# ATTAMI-Shield-serial.net
KiCad netlist of a schematic drawn in EAGLE
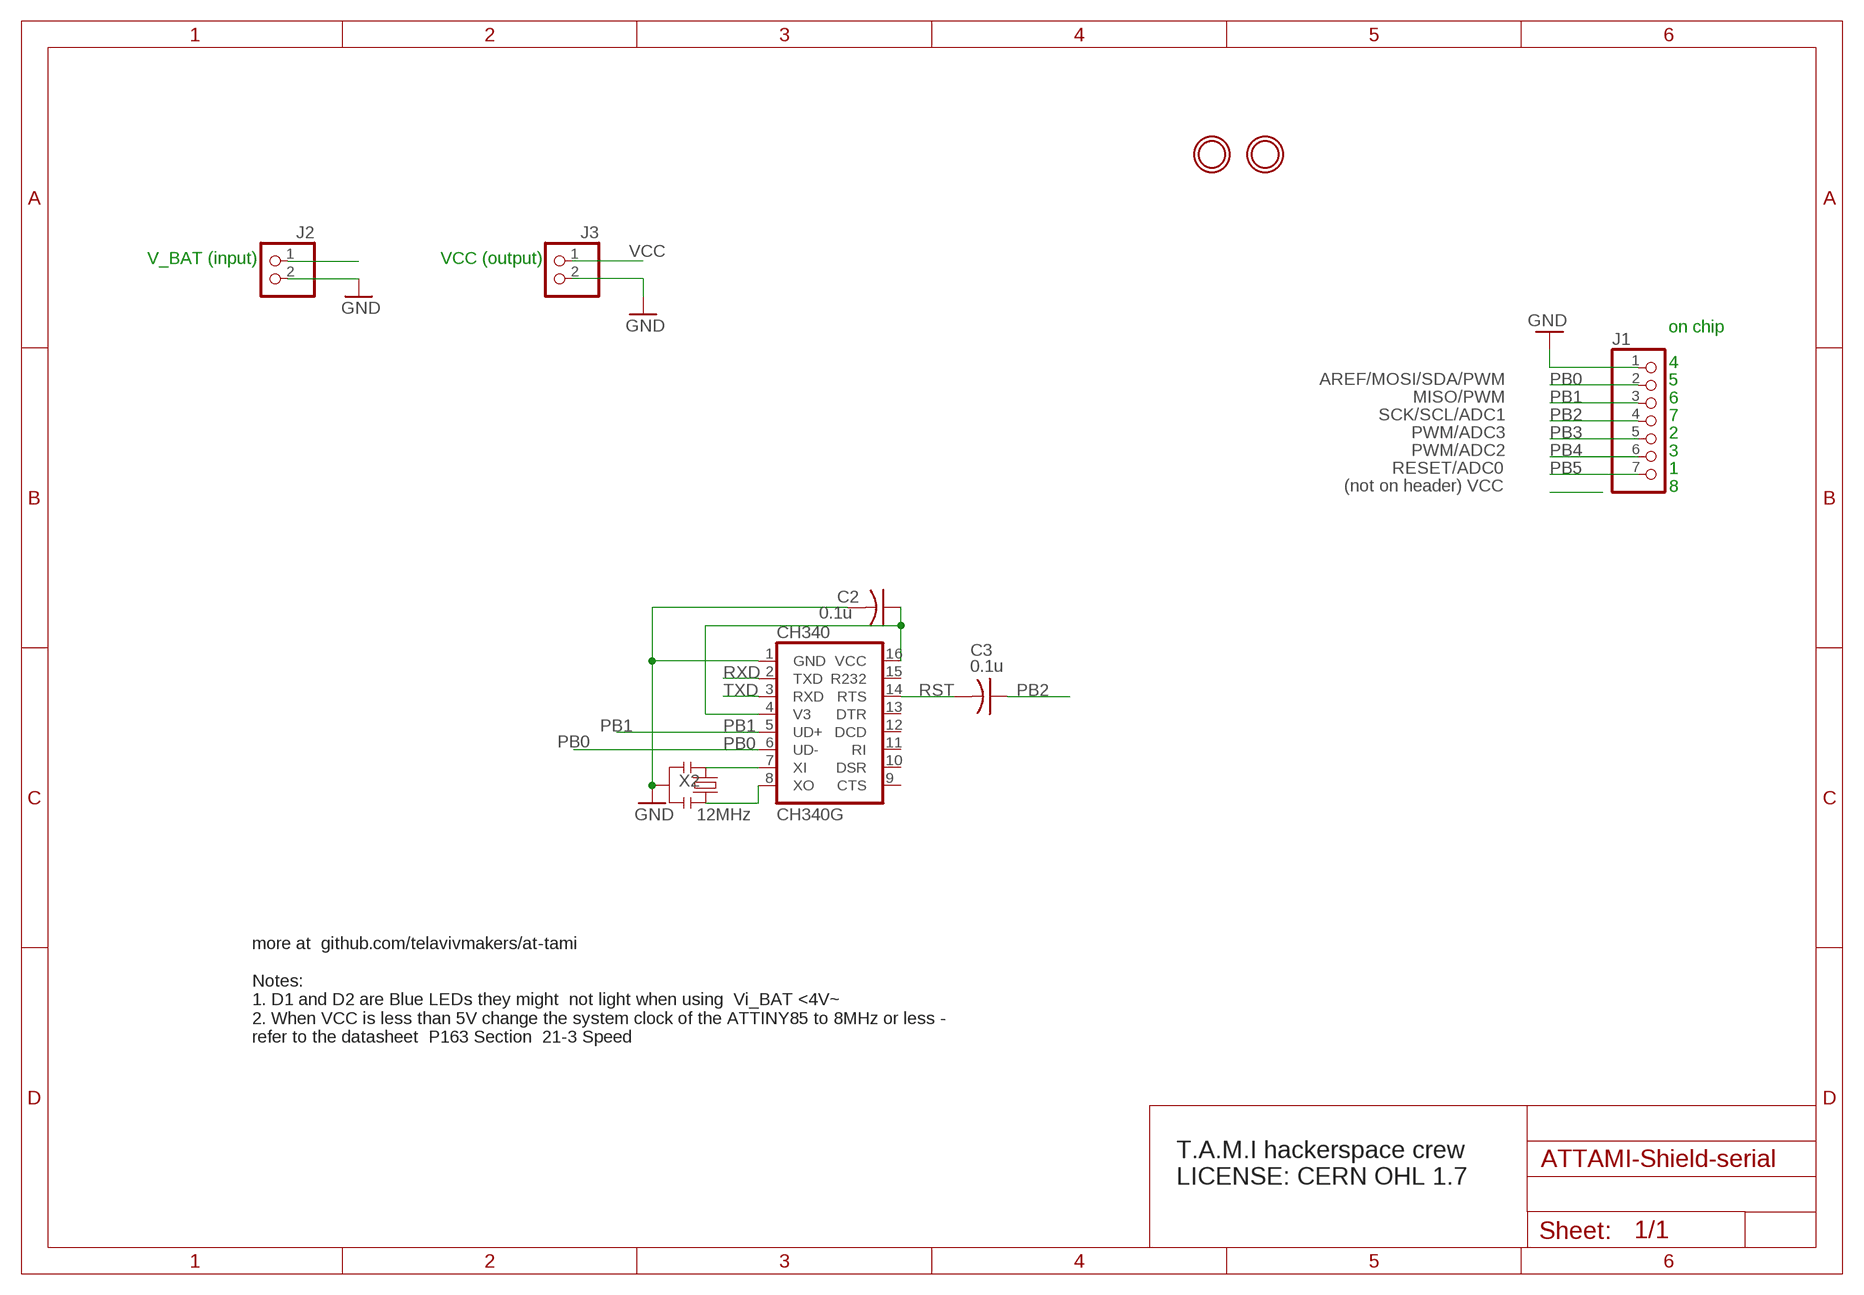
[diagram p0: schematic, sheet 1]

(export (version "E")
  (design (tool "Eeschema 10.0.6"))
  (components
    (comp (ref "C2")
      (value "0.1u")
      (footprint "eagle-import:C0603")
      (libsource (lib "eagle-import") (part "C-USC0603"))
    )
    (comp (ref "C3")
      (value "0.1u")
      (footprint "eagle-import:C0603")
      (libsource (lib "eagle-import") (part "C-USC0603"))
    )
    (comp (ref "CH340")
      (value "CH340G")
      (footprint "eagle-import:SO16")
      (libsource (lib "eagle-import") (part "CH340G"))
    )
    (comp (ref "J1")
      (value "HEADER-1X7ROUND")
      (footprint "eagle-import:1X07_ROUND")
      (libsource (lib "eagle-import") (part "HEADER-1X7ROUND"))
    )
    (comp (ref "J2")
      (value "HEADER-1X2ROUND")
      (footprint "eagle-import:1X02_ROUND")
      (libsource (lib "eagle-import") (part "HEADER-1X2ROUND"))
    )
    (comp (ref "J3")
      (value "HEADER-1X2ROUND")
      (footprint "eagle-import:1X02_ROUND")
      (libsource (lib "eagle-import") (part "HEADER-1X2ROUND"))
    )
    (comp (ref "U$1")
      (value "MOUNTINGHOLE2.0")
      (footprint "eagle-import:MOUNTINGHOLE_2.0_PLATED")
      (libsource (lib "eagle-import") (part "MOUNTINGHOLE2.0"))
    )
    (comp (ref "U$2")
      (value "MOUNTINGHOLE2.0")
      (footprint "eagle-import:MOUNTINGHOLE_2.0_PLATED")
      (libsource (lib "eagle-import") (part "MOUNTINGHOLE2.0"))
    )
    (comp (ref "X2")
      (value "12MHz")
      (footprint "eagle-import:RESONATOR-SMD")
      (libsource (lib "eagle-import") (part "RESONATORSMD"))
    )
  )
  (nets
    (net (code "1") (name "/PB0") (class "Default")
      (node (ref "CH340") (pin "6") (pinfunction "UD-_6") (pintype "bidirectional"))
      (node (ref "J1") (pin "2") (pinfunction "2_2") (pintype "passive"))
    )
    (net (code "2") (name "/PB1") (class "Default")
      (node (ref "CH340") (pin "5") (pinfunction "UD+_5") (pintype "bidirectional"))
      (node (ref "J1") (pin "3") (pinfunction "3_3") (pintype "passive"))
    )
    (net (code "3") (name "/PB2") (class "Default")
      (node (ref "C3") (pin "1") (pinfunction "1_1") (pintype "passive"))
      (node (ref "J1") (pin "4") (pinfunction "4_4") (pintype "passive"))
    )
    (net (code "4") (name "/PB3") (class "Default")
      (node (ref "J1") (pin "5") (pinfunction "5_5") (pintype "passive"))
    )
    (net (code "5") (name "/PB4") (class "Default")
      (node (ref "J1") (pin "6") (pinfunction "6_6") (pintype "passive"))
    )
    (net (code "6") (name "/PB5") (class "Default")
      (node (ref "J1") (pin "7") (pinfunction "7_7") (pintype "passive"))
    )
    (net (code "7") (name "/RST") (class "Default")
      (node (ref "C3") (pin "2") (pinfunction "2_2") (pintype "passive"))
      (node (ref "CH340") (pin "14") (pinfunction "RTS_14") (pintype "bidirectional"))
    )
    (net (code "8") (name "/RXD") (class "Default")
      (node (ref "CH340") (pin "2") (pinfunction "TXD_2") (pintype "bidirectional"))
    )
    (net (code "9") (name "/TXD") (class "Default")
      (node (ref "CH340") (pin "3") (pinfunction "RXD_3") (pintype "bidirectional"))
    )
    (net (code "10") (name "/VCC") (class "Default")
      (node (ref "C2") (pin "1") (pinfunction "1_1") (pintype "passive"))
      (node (ref "CH340") (pin "16") (pinfunction "VCC_16") (pintype "power_in"))
      (node (ref "CH340") (pin "4") (pinfunction "V3_4") (pintype "bidirectional"))
      (node (ref "J3") (pin "1") (pinfunction "1_1") (pintype "passive"))
    )
    (net (code "11") (name "GND") (class "Default")
      (node (ref "C2") (pin "2") (pinfunction "2_2") (pintype "passive"))
      (node (ref "CH340") (pin "1") (pinfunction "GND_1") (pintype "power_in"))
      (node (ref "J1") (pin "1") (pinfunction "1_1") (pintype "passive"))
      (node (ref "J2") (pin "2") (pinfunction "2_2") (pintype "passive"))
      (node (ref "J3") (pin "2") (pinfunction "2_2") (pintype "passive"))
      (node (ref "X2") (pin "2") (pinfunction "2_2") (pintype "passive"))
    )
    (net (code "12") (name "Net-(CH340-XI)") (class "Default")
      (node (ref "CH340") (pin "7") (pinfunction "XI_7") (pintype "bidirectional"))
      (node (ref "X2") (pin "1") (pinfunction "1_1") (pintype "passive"))
    )
    (net (code "13") (name "Net-(CH340-XO)") (class "Default")
      (node (ref "CH340") (pin "8") (pinfunction "XO_8") (pintype "bidirectional"))
      (node (ref "X2") (pin "3") (pinfunction "3_3") (pintype "passive"))
    )
    (net (code "14") (name "unconnected-(CH340-CTS-Pad9)") (class "Default")
      (node (ref "CH340") (pin "9") (pinfunction "CTS_9") (pintype "bidirectional"))
    )
    (net (code "15") (name "unconnected-(CH340-DCD-Pad12)") (class "Default")
      (node (ref "CH340") (pin "12") (pinfunction "DCD_12") (pintype "bidirectional"))
    )
    (net (code "16") (name "unconnected-(CH340-DSR-Pad10)") (class "Default")
      (node (ref "CH340") (pin "10") (pinfunction "DSR_10") (pintype "bidirectional"))
    )
    (net (code "17") (name "unconnected-(CH340-DTR-Pad13)") (class "Default")
      (node (ref "CH340") (pin "13") (pinfunction "DTR_13") (pintype "bidirectional"))
    )
    (net (code "18") (name "unconnected-(CH340-R232-Pad15)") (class "Default")
      (node (ref "CH340") (pin "15") (pinfunction "R232_15") (pintype "bidirectional"))
    )
    (net (code "19") (name "unconnected-(CH340-RI-Pad11)") (class "Default")
      (node (ref "CH340") (pin "11") (pinfunction "RI_11") (pintype "bidirectional"))
    )
    (net (code "20") (name "unconnected-(J2-Pad1)") (class "Default")
      (node (ref "J2") (pin "1") (pinfunction "1_1") (pintype "passive"))
    )
  )
)
